# MotionSense.net
KiCad netlist of a schematic drawn in Altium Designer
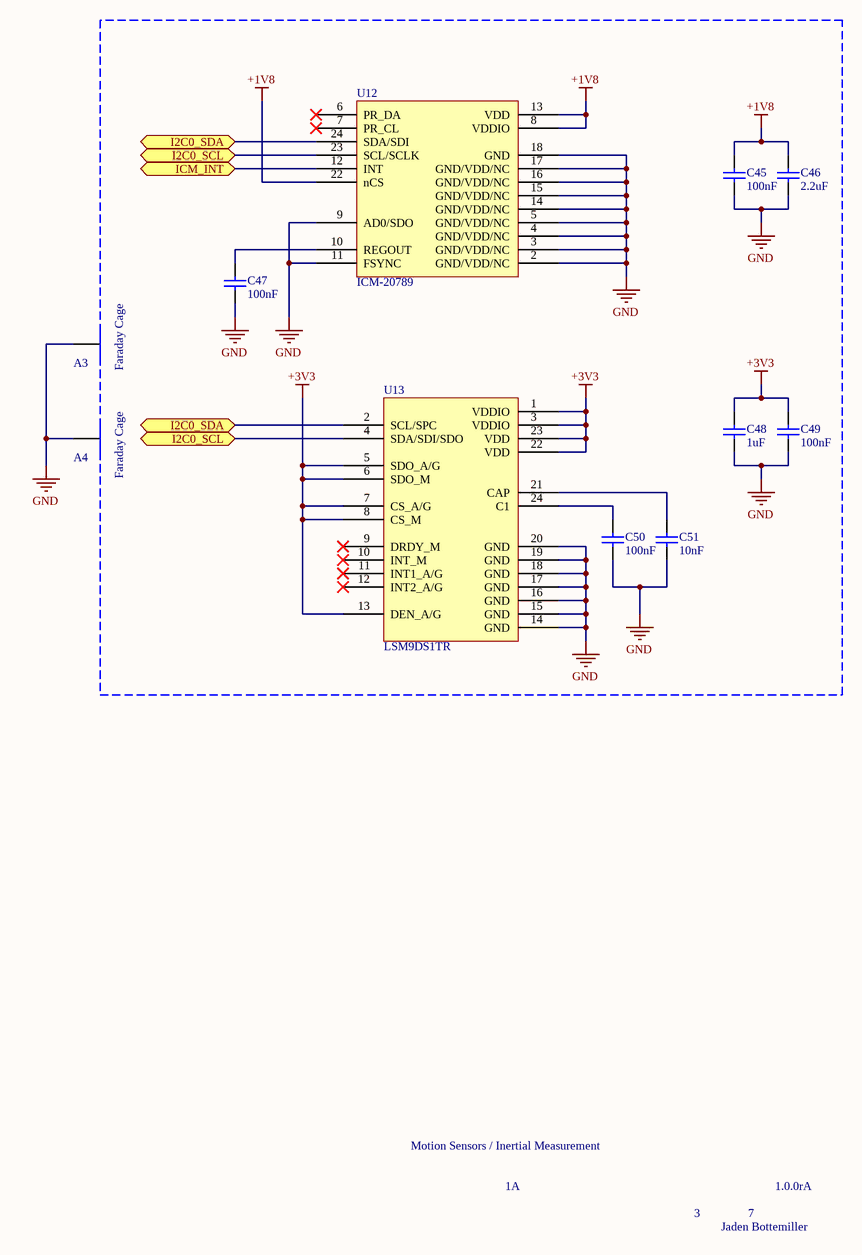
[diagram p0: MotionSense.SchDoc]

(export (version "E")
  (design (tool "Eeschema 10.0.6"))
  (components
    (comp (ref "A3")
      (value "Faraday Cage")
      (description "Standard Faraday Cage")
      (libsource (lib "NikoboticsLib") (part "Faraday Cage"))
    )
    (comp (ref "A4")
      (value "Faraday Cage")
      (description "Standard Faraday Cage")
      (libsource (lib "NikoboticsLib") (part "Faraday Cage"))
    )
    (comp (ref "C45")
      (value "100nF")
      (description "Standard Capacitor")
      (fields (field (name "Comment") "CAP"))
      (libsource (lib "NikoboticsLib") (part "CAP"))
    )
    (comp (ref "C46")
      (value "2.2uF")
      (description "Standard Capacitor")
      (fields (field (name "Comment") "CAP"))
      (libsource (lib "NikoboticsLib") (part "CAP"))
    )
    (comp (ref "C47")
      (value "100nF")
      (description "Standard Capacitor")
      (fields (field (name "Comment") "CAP"))
      (libsource (lib "NikoboticsLib") (part "CAP"))
    )
    (comp (ref "C48")
      (value "1uF")
      (description "Standard Capacitor")
      (fields (field (name "Comment") "CAP"))
      (libsource (lib "NikoboticsLib") (part "CAP"))
    )
    (comp (ref "C49")
      (value "100nF")
      (description "Standard Capacitor")
      (fields (field (name "Comment") "CAP"))
      (libsource (lib "NikoboticsLib") (part "CAP"))
    )
    (comp (ref "C50")
      (value "100nF")
      (description "Standard Capacitor")
      (fields (field (name "Comment") "CAP"))
      (libsource (lib "NikoboticsLib") (part "CAP"))
    )
    (comp (ref "C51")
      (value "10nF")
      (description "Standard Capacitor")
      (fields (field (name "Comment") "CAP"))
      (libsource (lib "NikoboticsLib") (part "CAP"))
    )
    (comp (ref "U12")
      (value "ICM-20789")
      (description "Accelerometer, Gyroscope, Barometric Pressure Sensor. 3-Axis I2C")
      (libsource (lib "NikoboticsLib") (part "ICM-20789"))
    )
    (comp (ref "U13")
      (value "LSM9DS1TR")
      (description "Accelerometer, Gyroscope, Magnetometer, Temperature, 3 Axis Sensor I²C, SPI Output")
      (libsource (lib "NikoboticsLib") (part "LSM9DS1TR"))
    )
  )
  (nets
    (net (code "1") (name "+1V8") (class "Default")
      (node (ref "C45") (pin "2") (pinfunction "2_2") (pintype "passive"))
      (node (ref "C46") (pin "2") (pinfunction "2_2") (pintype "passive"))
      (node (ref "U12") (pin "13") (pinfunction "VDD_13") (pintype "passive"))
      (node (ref "U12") (pin "22") (pinfunction "nCS_22") (pintype "passive"))
      (node (ref "U12") (pin "8") (pinfunction "VDDIO_8") (pintype "passive"))
    )
    (net (code "2") (name "+3V3") (class "Default")
      (node (ref "C48") (pin "2") (pinfunction "2_2") (pintype "passive"))
      (node (ref "C49") (pin "2") (pinfunction "2_2") (pintype "passive"))
      (node (ref "U13") (pin "1") (pinfunction "VDDIO_1") (pintype "passive"))
      (node (ref "U13") (pin "13") (pinfunction "DEN_A/G_13") (pintype "passive"))
      (node (ref "U13") (pin "22") (pinfunction "VDD_22") (pintype "passive"))
      (node (ref "U13") (pin "23") (pinfunction "VDD_23") (pintype "passive"))
      (node (ref "U13") (pin "3") (pinfunction "VDDIO_3") (pintype "passive"))
      (node (ref "U13") (pin "5") (pinfunction "SDO_A/G_5") (pintype "passive"))
      (node (ref "U13") (pin "6") (pinfunction "SDO_M_6") (pintype "passive"))
      (node (ref "U13") (pin "7") (pinfunction "CS_A/G_7") (pintype "passive"))
      (node (ref "U13") (pin "8") (pinfunction "CS_M_8") (pintype "passive"))
    )
    (net (code "3") (name "/I2C0_SCL") (class "Default")
      (node (ref "U12") (pin "23") (pinfunction "SCL/SCLK_23") (pintype "passive"))
      (node (ref "U13") (pin "4") (pinfunction "SDA/SDI/SDO_4") (pintype "passive"))
    )
    (net (code "4") (name "/I2C0_SDA") (class "Default")
      (node (ref "U12") (pin "24") (pinfunction "SDA/SDI_24") (pintype "passive"))
      (node (ref "U13") (pin "2") (pinfunction "SCL/SPC_2") (pintype "passive"))
    )
    (net (code "5") (name "/ICM_INT") (class "Default")
      (node (ref "U12") (pin "12") (pinfunction "INT_12") (pintype "passive"))
    )
    (net (code "6") (name "GND") (class "Default")
      (node (ref "A3") (pin "1") (pinfunction "Pin_1") (pintype "passive"))
      (node (ref "A4") (pin "1") (pinfunction "Pin_1") (pintype "passive"))
      (node (ref "C45") (pin "1") (pinfunction "1_1") (pintype "passive"))
      (node (ref "C46") (pin "1") (pinfunction "1_1") (pintype "passive"))
      (node (ref "C47") (pin "1") (pinfunction "1_1") (pintype "passive"))
      (node (ref "C48") (pin "1") (pinfunction "1_1") (pintype "passive"))
      (node (ref "C49") (pin "1") (pinfunction "1_1") (pintype "passive"))
      (node (ref "C50") (pin "1") (pinfunction "1_1") (pintype "passive"))
      (node (ref "C51") (pin "1") (pinfunction "1_1") (pintype "passive"))
      (node (ref "U12") (pin "11") (pinfunction "FSYNC_11") (pintype "passive"))
      (node (ref "U12") (pin "14") (pinfunction "GND/VDD/NC_14") (pintype "passive"))
      (node (ref "U12") (pin "15") (pinfunction "GND/VDD/NC_15") (pintype "passive"))
      (node (ref "U12") (pin "16") (pinfunction "GND/VDD/NC_16") (pintype "passive"))
      (node (ref "U12") (pin "17") (pinfunction "GND/VDD/NC_17") (pintype "passive"))
      (node (ref "U12") (pin "18") (pinfunction "GND_18") (pintype "passive"))
      (node (ref "U12") (pin "2") (pinfunction "GND/VDD/NC_2") (pintype "passive"))
      (node (ref "U12") (pin "3") (pinfunction "GND/VDD/NC_3") (pintype "passive"))
      (node (ref "U12") (pin "4") (pinfunction "GND/VDD/NC_4") (pintype "passive"))
      (node (ref "U12") (pin "5") (pinfunction "GND/VDD/NC_5") (pintype "passive"))
      (node (ref "U12") (pin "9") (pinfunction "AD0/SDO_9") (pintype "passive"))
      (node (ref "U13") (pin "14") (pinfunction "GND_14") (pintype "passive"))
      (node (ref "U13") (pin "15") (pinfunction "GND_15") (pintype "passive"))
      (node (ref "U13") (pin "16") (pinfunction "GND_16") (pintype "passive"))
      (node (ref "U13") (pin "17") (pinfunction "GND_17") (pintype "passive"))
      (node (ref "U13") (pin "18") (pinfunction "GND_18") (pintype "passive"))
      (node (ref "U13") (pin "19") (pinfunction "GND_19") (pintype "passive"))
      (node (ref "U13") (pin "20") (pinfunction "GND_20") (pintype "passive"))
    )
    (net (code "7") (name "Net-(U12-REGOUT)") (class "Default")
      (node (ref "C47") (pin "2") (pinfunction "2_2") (pintype "passive"))
      (node (ref "U12") (pin "10") (pinfunction "REGOUT_10") (pintype "passive"))
    )
    (net (code "8") (name "Net-(U13-C1)") (class "Default")
      (node (ref "C50") (pin "2") (pinfunction "2_2") (pintype "passive"))
      (node (ref "U13") (pin "24") (pinfunction "C1_24") (pintype "passive"))
    )
    (net (code "9") (name "Net-(U13-CAP)") (class "Default")
      (node (ref "C51") (pin "2") (pinfunction "2_2") (pintype "passive"))
      (node (ref "U13") (pin "21") (pinfunction "CAP_21") (pintype "passive"))
    )
    (net (code "10") (name "unconnected-(U12-NC-Pad1)") (class "Default")
      (node (ref "U12") (pin "1") (pinfunction "NC_1") (pintype "passive"))
    )
    (net (code "11") (name "unconnected-(U12-NC-Pad19)") (class "Default")
      (node (ref "U12") (pin "19") (pinfunction "NC_19") (pintype "passive"))
    )
    (net (code "12") (name "unconnected-(U12-NC-Pad20)") (class "Default")
      (node (ref "U12") (pin "20") (pinfunction "NC_20") (pintype "passive"))
    )
    (net (code "13") (name "unconnected-(U12-NC-Pad21)") (class "Default")
      (node (ref "U12") (pin "21") (pinfunction "NC_21") (pintype "passive"))
    )
    (net (code "14") (name "unconnected-(U12-PR_CL-Pad7)") (class "Default")
      (node (ref "U12") (pin "7") (pinfunction "PR_CL_7") (pintype "passive+no_connect"))
    )
    (net (code "15") (name "unconnected-(U12-PR_DA-Pad6)") (class "Default")
      (node (ref "U12") (pin "6") (pinfunction "PR_DA_6") (pintype "passive+no_connect"))
    )
    (net (code "16") (name "unconnected-(U13-DRDY_M-Pad9)") (class "Default")
      (node (ref "U13") (pin "9") (pinfunction "DRDY_M_9") (pintype "passive+no_connect"))
    )
    (net (code "17") (name "unconnected-(U13-INT1_A{slash}G-Pad11)") (class "Default")
      (node (ref "U13") (pin "11") (pinfunction "INT1_A/G_11") (pintype "passive+no_connect"))
    )
    (net (code "18") (name "unconnected-(U13-INT2_A{slash}G-Pad12)") (class "Default")
      (node (ref "U13") (pin "12") (pinfunction "INT2_A/G_12") (pintype "passive+no_connect"))
    )
    (net (code "19") (name "unconnected-(U13-INT_M-Pad10)") (class "Default")
      (node (ref "U13") (pin "10") (pinfunction "INT_M_10") (pintype "passive+no_connect"))
    )
  )
)
